# shcmeatic_sst.net
KiCad netlist of a schematic drawn in Altium Designer
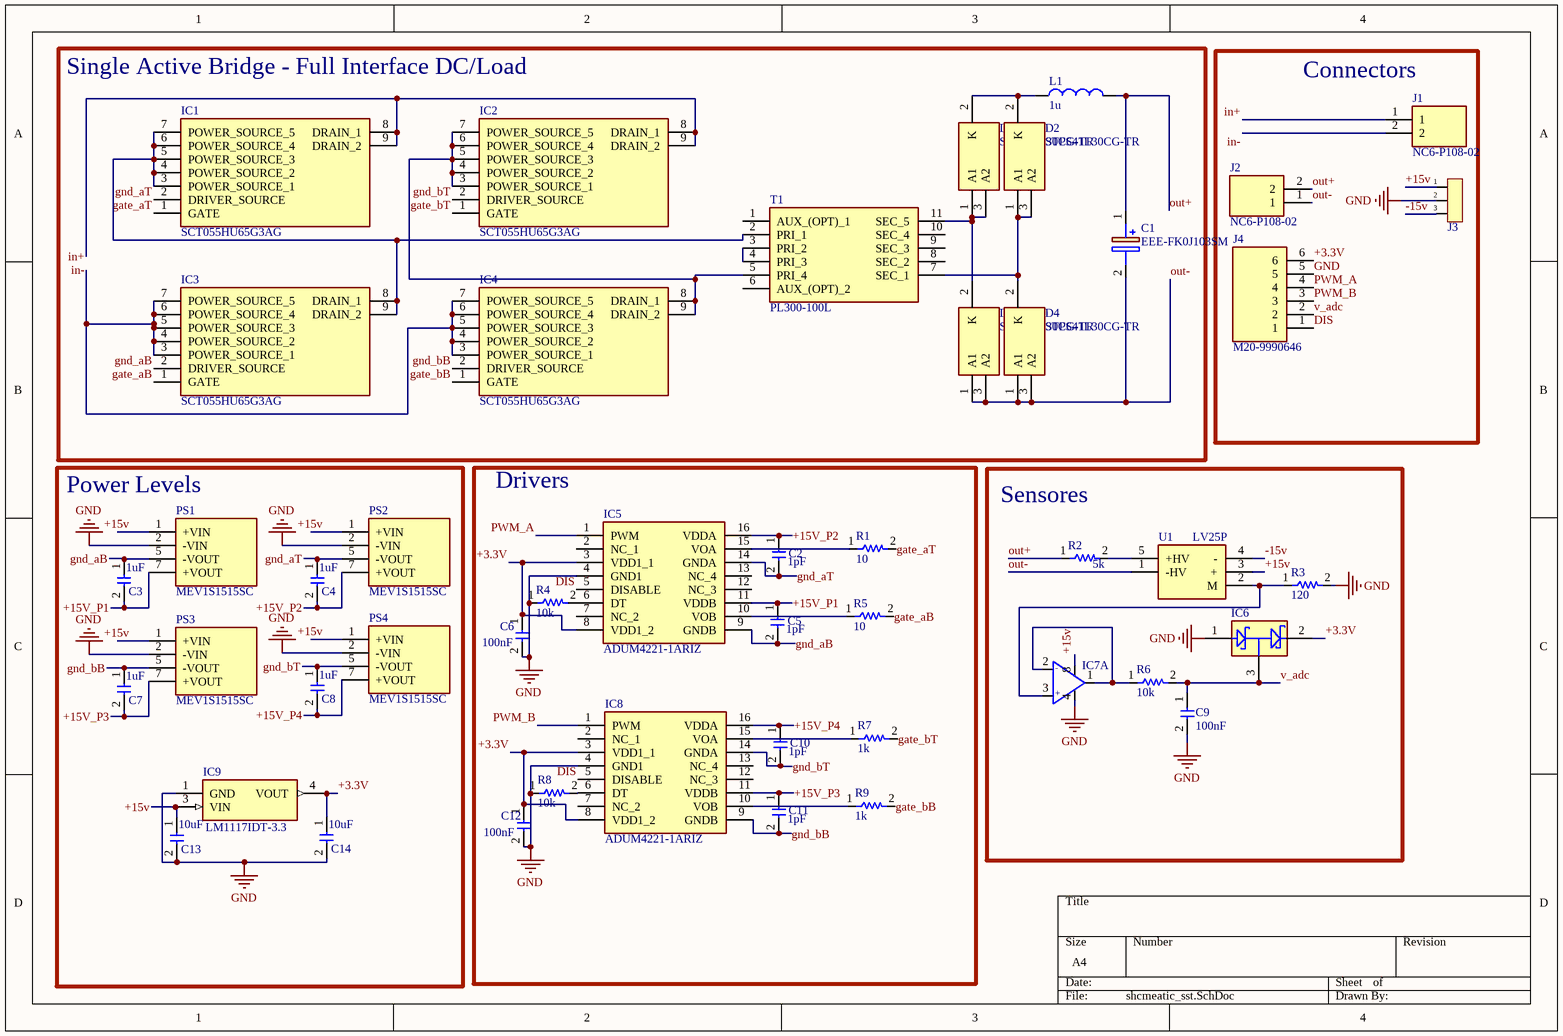
[diagram p0: shcmeatic_sst.SchDoc]

(export (version "E")
  (design (tool "Eeschema 10.0.6"))
  (components
    (comp (ref "C1")
      (value "EEE-FK0J103SM")
      (footprint "r60_mkt_10_100_capacitor_10uF")
      (description "Capacitor Polarised")
      (fields (field (name "MOUSER PART NUMBER") "667-EEE-FK0J103SM"))
      (libsource (lib "*") (part "EEE-FK0J103SM"))
    )
    (comp (ref "C2")
      (value "1pF")
      (footprint "SamacSys:C1206")
      (libsource (lib "Schlib1") (part "Capacitor"))
    )
    (comp (ref "C3")
      (value "1uF")
      (footprint "SamacSys:C1206")
      (libsource (lib "Schlib1") (part "Capacitor"))
    )
    (comp (ref "C4")
      (value "1uF")
      (footprint "SamacSys:C1206")
      (libsource (lib "Schlib1") (part "Capacitor"))
    )
    (comp (ref "C5")
      (value "1pF")
      (footprint "SamacSys:C1206")
      (libsource (lib "Schlib1") (part "Capacitor"))
    )
    (comp (ref "C6")
      (value "100nF")
      (footprint "SamacSys:C1206")
      (libsource (lib "Schlib1") (part "Capacitor"))
    )
    (comp (ref "C7")
      (value "1uF")
      (footprint "SamacSys:C1206")
      (libsource (lib "Schlib1") (part "Capacitor"))
    )
    (comp (ref "C8")
      (value "1uF")
      (footprint "SamacSys:C1206")
      (libsource (lib "Schlib1") (part "Capacitor"))
    )
    (comp (ref "C9")
      (value "100nF")
      (footprint "SamacSys:C1206")
      (libsource (lib "Schlib1") (part "Capacitor"))
    )
    (comp (ref "C10")
      (value "1pF")
      (footprint "SamacSys:C1206")
      (libsource (lib "Schlib1") (part "Capacitor"))
    )
    (comp (ref "C11")
      (value "1pF")
      (footprint "SamacSys:C1206")
      (libsource (lib "Schlib1") (part "Capacitor"))
    )
    (comp (ref "C12")
      (value "100nF")
      (footprint "SamacSys:C1206")
      (libsource (lib "Schlib1") (part "Capacitor"))
    )
    (comp (ref "C13")
      (value "10uF")
      (footprint "T491C")
      (description "tantalum")
      (libsource (lib "Schlib1") (part "Capacitor"))
    )
    (comp (ref "C14")
      (value "10uF")
      (footprint "T491C")
      (description "Tantalum")
      (libsource (lib "Schlib1") (part "Capacitor"))
    )
    (comp (ref "D1")
      (value "STPS41L30CG-TR")
      (footprint "SamacSys:STPS41L30CGTR")
      (description "Schottky Diode")
      (fields (field (name "MOUSER PART NUMBER") "511-STPS41L30CG-TR"))
      (libsource (lib "*") (part "STPS41L30CG-TR"))
    )
    (comp (ref "D2")
      (value "STPS41L30CG-TR")
      (footprint "SamacSys:STPS41L30CGTR")
      (description "Schottky Diode")
      (fields (field (name "MOUSER PART NUMBER") "511-STPS41L30CG-TR"))
      (libsource (lib "*") (part "STPS41L30CG-TR"))
    )
    (comp (ref "D3")
      (value "STPS41L30CG-TR")
      (footprint "SamacSys:STPS41L30CGTR")
      (description "Schottky Diode")
      (fields (field (name "MOUSER PART NUMBER") "511-STPS41L30CG-TR"))
      (libsource (lib "*") (part "STPS41L30CG-TR"))
    )
    (comp (ref "D4")
      (value "STPS41L30CG-TR")
      (footprint "SamacSys:STPS41L30CGTR")
      (description "Schottky Diode")
      (fields (field (name "MOUSER PART NUMBER") "511-STPS41L30CG-TR"))
      (libsource (lib "*") (part "STPS41L30CG-TR"))
    )
    (comp (ref "IC1")
      (value "SCT055HU65G3AG")
      (footprint "SamacSys:SCT055HU65G3AG")
      (description "Integrated Circuit")
      (fields (field (name "MOUSER PART NUMBER") "511-SCT055HU65G3AG"))
      (libsource (lib "*") (part "SCT055HU65G3AG"))
    )
    (comp (ref "IC2")
      (value "SCT055HU65G3AG")
      (footprint "SamacSys:SCT055HU65G3AG")
      (description "Integrated Circuit")
      (fields (field (name "MOUSER PART NUMBER") "511-SCT055HU65G3AG"))
      (libsource (lib "*") (part "SCT055HU65G3AG"))
    )
    (comp (ref "IC3")
      (value "SCT055HU65G3AG")
      (footprint "SamacSys:SCT055HU65G3AG")
      (description "Integrated Circuit")
      (fields (field (name "MOUSER PART NUMBER") "511-SCT055HU65G3AG"))
      (libsource (lib "*") (part "SCT055HU65G3AG"))
    )
    (comp (ref "IC4")
      (value "SCT055HU65G3AG")
      (footprint "SamacSys:SCT055HU65G3AG")
      (description "Integrated Circuit")
      (fields (field (name "MOUSER PART NUMBER") "511-SCT055HU65G3AG"))
      (libsource (lib "*") (part "SCT055HU65G3AG"))
    )
    (comp (ref "IC5")
      (value "ADUM4221-1ARIZ")
      (footprint "SamacSys:SOIC127P1030X264-16N")
      (description "Integrated Circuit")
      (fields (field (name "MOUSER PART NUMBER") "584-ADUM4221-1ARIZ"))
      (libsource (lib "*") (part "ADUM4221-1ARIZ"))
    )
    (comp (ref "IC6") (value "bat54s") (footprint "BAT54S") (libsource (lib "Schlib1") (part "bat54s")))
    (comp (ref "IC7") (value "TSX712IDT") (footprint "SO-8") (libsource (lib "Schlib1") (part "TSX712IDT")))
    (comp (ref "IC8")
      (value "ADUM4221-1ARIZ")
      (footprint "SamacSys:SOIC127P1030X264-16N")
      (description "Integrated Circuit")
      (fields (field (name "MOUSER PART NUMBER") "584-ADUM4221-1ARIZ"))
      (libsource (lib "*") (part "ADUM4221-1ARIZ"))
    )
    (comp (ref "IC9")
      (value "LM1117IDT-3.3")
      (footprint "SamacSys:TO228P991X238-3N")
      (description "Integrated Circuit")
      (fields (field (name "MOUSER PART NUMBER") "926-LM1117IDT-33"))
      (libsource (lib "*") (part "LM1117IDT-3.3"))
    )
    (comp (ref "J1")
      (value "NC6-P108-02")
      (footprint "SamacSys:NC6P10802")
      (description "Connector")
      (fields (field (name "MOUSER PART NUMBER") "571-314376640"))
      (libsource (lib "") (part "NC6-P108-02_1"))
    )
    (comp (ref "J2")
      (value "NC6-P108-02")
      (footprint "SamacSys:NC6P10802")
      (description "Connector")
      (fields (field (name "MOUSER PART NUMBER") "571-314376640"))
      (libsource (lib "*") (part "NC6-P108-02"))
    )
    (comp (ref "J3")
      (value "Conector 1x3P")
      (footprint "Conector 1x3 Screw")
      (libsource (lib "Schlib1") (part "Conector 1x3P"))
    )
    (comp (ref "J4")
      (value "M20-9990646")
      (footprint "SamacSys:HDRV6W64P0X254_1X6_1524X254X864P")
      (description "Connector")
      (fields (field (name "MOUSER PART NUMBER") "855-M20-9990646"))
      (libsource (lib "*") (part "M20-9990646"))
    )
    (comp (ref "L1")
      (value "1u")
      (footprint "bobine_handmade_20mm_diam")
      (description "Inductor")
      (libsource (lib "Simulation Generic Components") (part "Inductor"))
    )
    (comp (ref "PS1")
      (value "MEV1S1515SC")
      (footprint "SamacSys:MEV1S1515SC")
      (description "Power Supply")
      (fields (field (name "MOUSER PART NUMBER") "580-MEV1S1515SC"))
      (libsource (lib "*") (part "MEV1S1515SC"))
    )
    (comp (ref "PS2")
      (value "MEV1S1515SC")
      (footprint "SamacSys:MEV1S1515SC")
      (description "Power Supply")
      (fields (field (name "MOUSER PART NUMBER") "580-MEV1S1515SC"))
      (libsource (lib "*") (part "MEV1S1515SC"))
    )
    (comp (ref "PS3")
      (value "MEV1S1515SC")
      (footprint "SamacSys:MEV1S1515SC")
      (description "Power Supply")
      (fields (field (name "MOUSER PART NUMBER") "580-MEV1S1515SC"))
      (libsource (lib "*") (part "MEV1S1515SC"))
    )
    (comp (ref "PS4")
      (value "MEV1S1515SC")
      (footprint "SamacSys:MEV1S1515SC")
      (description "Power Supply")
      (fields (field (name "MOUSER PART NUMBER") "580-MEV1S1515SC"))
      (libsource (lib "*") (part "MEV1S1515SC"))
    )
    (comp (ref "R1")
      (value "10")
      (footprint "SamacSys:RESC3216X75N")
      (libsource (lib "Schlib1") (part "Resistor"))
    )
    (comp (ref "R2")
      (value "5k")
      (footprint "SamacSys:RESC3216X75N")
      (description "140 mW")
      (libsource (lib "Schlib1") (part "Resistor"))
    )
    (comp (ref "R3")
      (value "120")
      (footprint "SamacSys:RESC3216X75N")
      (description "82.5 mW")
      (libsource (lib "Schlib1") (part "Resistor"))
    )
    (comp (ref "R4")
      (value "10k")
      (footprint "SamacSys:RESC3216X75N")
      (libsource (lib "Schlib1") (part "Resistor"))
    )
    (comp (ref "R5")
      (value "10")
      (footprint "SamacSys:RESC3216X75N")
      (libsource (lib "Schlib1") (part "Resistor"))
    )
    (comp (ref "R6")
      (value "10k")
      (footprint "SamacSys:RESC3216X75N")
      (libsource (lib "Schlib1") (part "Resistor"))
    )
    (comp (ref "R7")
      (value "1k")
      (footprint "SamacSys:RESC3216X75N")
      (libsource (lib "Schlib1") (part "Resistor"))
    )
    (comp (ref "R8")
      (value "10k")
      (footprint "SamacSys:RESC3216X75N")
      (libsource (lib "Schlib1") (part "Resistor"))
    )
    (comp (ref "R9")
      (value "1k")
      (footprint "SamacSys:RESC3216X75N")
      (libsource (lib "Schlib1") (part "Resistor"))
    )
    (comp (ref "T1")
      (value "PL300-100L")
      (footprint "SamacSys:PL300100L")
      (description "Transformer")
      (fields (field (name "MOUSER PART NUMBER") "994-PL300-100L"))
      (libsource (lib "*") (part "PL300-100L"))
    )
    (comp (ref "U1")
      (value "LV25P")
      (footprint "LV-25-P/LV-20-P")
      (description "Undefined or Miscellaneous")
      (libsource (lib "Schlib1") (part "LV25P"))
    )
  )
  (nets
    (net (code "1") (name "/+3.3V") (class "Default")
      (node (ref "C12") (pin "1") (pinfunction "1_1") (pintype "passive"))
      (node (ref "C14") (pin "1") (pinfunction "1_1") (pintype "passive"))
      (node (ref "C6") (pin "1") (pinfunction "1_1") (pintype "passive"))
      (node (ref "IC5") (pin "3") (pinfunction "VDD1_1_3") (pintype "passive"))
      (node (ref "IC5") (pin "8") (pinfunction "VDD1_2_8") (pintype "passive"))
      (node (ref "IC6") (pin "2") (pinfunction "OUT_2") (pintype "passive"))
      (node (ref "IC8") (pin "3") (pinfunction "VDD1_1_3") (pintype "passive"))
      (node (ref "IC8") (pin "8") (pinfunction "VDD1_2_8") (pintype "passive"))
      (node (ref "IC9") (pin "4") (pinfunction "VOUT_4") (pintype "output"))
      (node (ref "J4") (pin "6") (pinfunction "6_6") (pintype "passive"))
    )
    (net (code "2") (name "/+15V_P1") (class "Default")
      (node (ref "C3") (pin "2") (pinfunction "2_2") (pintype "passive"))
      (node (ref "C5") (pin "1") (pinfunction "1_1") (pintype "passive"))
      (node (ref "IC5") (pin "11") (pinfunction "VDDB_11") (pintype "passive"))
      (node (ref "PS1") (pin "7") (pinfunction "+VOUT_7") (pintype "passive"))
    )
    (net (code "3") (name "/+15V_P2") (class "Default")
      (node (ref "C2") (pin "1") (pinfunction "1_1") (pintype "passive"))
      (node (ref "C4") (pin "2") (pinfunction "2_2") (pintype "passive"))
      (node (ref "IC5") (pin "16") (pinfunction "VDDA_16") (pintype "passive"))
      (node (ref "PS2") (pin "7") (pinfunction "+VOUT_7") (pintype "passive"))
    )
    (net (code "4") (name "/+15V_P3") (class "Default")
      (node (ref "C11") (pin "1") (pinfunction "1_1") (pintype "passive"))
      (node (ref "C7") (pin "2") (pinfunction "2_2") (pintype "passive"))
      (node (ref "IC8") (pin "11") (pinfunction "VDDB_11") (pintype "passive"))
      (node (ref "PS3") (pin "7") (pinfunction "+VOUT_7") (pintype "passive"))
    )
    (net (code "5") (name "/+15V_P4") (class "Default")
      (node (ref "C10") (pin "1") (pinfunction "1_1") (pintype "passive"))
      (node (ref "C8") (pin "2") (pinfunction "2_2") (pintype "passive"))
      (node (ref "IC8") (pin "16") (pinfunction "VDDA_16") (pintype "passive"))
      (node (ref "PS4") (pin "7") (pinfunction "+VOUT_7") (pintype "passive"))
    )
    (net (code "6") (name "/+15v") (class "Default")
      (node (ref "C13") (pin "1") (pinfunction "1_1") (pintype "passive"))
      (node (ref "IC7") (pin "8") (pinfunction "8_8") (pintype "passive"))
      (node (ref "IC9") (pin "3") (pinfunction "VIN_3") (pintype "input"))
      (node (ref "J3") (pin "1") (pinfunction "1_1") (pintype "passive"))
      (node (ref "PS1") (pin "1") (pinfunction "+VIN_1") (pintype "passive"))
      (node (ref "PS2") (pin "1") (pinfunction "+VIN_1") (pintype "passive"))
      (node (ref "PS3") (pin "1") (pinfunction "+VIN_1") (pintype "passive"))
      (node (ref "PS4") (pin "1") (pinfunction "+VIN_1") (pintype "passive"))
      (node (ref "U1") (pin "3") (pinfunction "+_3") (pintype "passive"))
    )
    (net (code "7") (name "/-15v") (class "Default")
      (node (ref "J3") (pin "3") (pinfunction "3_3") (pintype "passive"))
      (node (ref "U1") (pin "4") (pinfunction "-_4") (pintype "passive"))
    )
    (net (code "9") (name "/DIS") (class "Default")
      (node (ref "IC5") (pin "5") (pinfunction "DISABLE_5") (pintype "passive"))
      (node (ref "IC8") (pin "5") (pinfunction "DISABLE_5") (pintype "passive"))
      (node (ref "J4") (pin "1") (pinfunction "1_1") (pintype "passive"))
    )
    (net (code "10") (name "/PWM_A") (class "Default")
      (node (ref "IC5") (pin "1") (pinfunction "PWM_1") (pintype "passive"))
      (node (ref "J4") (pin "4") (pinfunction "4_4") (pintype "passive"))
    )
    (net (code "11") (name "/PWM_B") (class "Default")
      (node (ref "IC8") (pin "1") (pinfunction "PWM_1") (pintype "passive"))
      (node (ref "J4") (pin "3") (pinfunction "3_3") (pintype "passive"))
    )
    (net (code "12") (name "/gate_aB") (class "Default")
      (node (ref "IC3") (pin "1") (pinfunction "GATE_1") (pintype "passive"))
      (node (ref "R5") (pin "2") (pinfunction "2_2") (pintype "passive"))
    )
    (net (code "13") (name "/gate_aT") (class "Default")
      (node (ref "IC1") (pin "1") (pinfunction "GATE_1") (pintype "passive"))
      (node (ref "R1") (pin "2") (pinfunction "2_2") (pintype "passive"))
    )
    (net (code "14") (name "/gate_bB") (class "Default")
      (node (ref "IC4") (pin "1") (pinfunction "GATE_1") (pintype "passive"))
      (node (ref "R9") (pin "2") (pinfunction "2_2") (pintype "passive"))
    )
    (net (code "15") (name "/gate_bT") (class "Default")
      (node (ref "IC2") (pin "1") (pinfunction "GATE_1") (pintype "passive"))
      (node (ref "R7") (pin "2") (pinfunction "2_2") (pintype "passive"))
    )
    (net (code "16") (name "/gnd_aB") (class "Default")
      (node (ref "C3") (pin "1") (pinfunction "1_1") (pintype "passive"))
      (node (ref "C5") (pin "2") (pinfunction "2_2") (pintype "passive"))
      (node (ref "IC3") (pin "2") (pinfunction "DRIVER_SOURCE_2") (pintype "passive"))
      (node (ref "IC5") (pin "9") (pinfunction "GNDB_9") (pintype "passive"))
      (node (ref "PS1") (pin "5") (pinfunction "-VOUT_5") (pintype "passive"))
    )
    (net (code "17") (name "/gnd_aT") (class "Default")
      (node (ref "C2") (pin "2") (pinfunction "2_2") (pintype "passive"))
      (node (ref "C4") (pin "1") (pinfunction "1_1") (pintype "passive"))
      (node (ref "IC1") (pin "2") (pinfunction "DRIVER_SOURCE_2") (pintype "passive"))
      (node (ref "IC5") (pin "14") (pinfunction "GNDA_14") (pintype "passive"))
      (node (ref "PS2") (pin "5") (pinfunction "-VOUT_5") (pintype "passive"))
    )
    (net (code "18") (name "/gnd_bB") (class "Default")
      (node (ref "C11") (pin "2") (pinfunction "2_2") (pintype "passive"))
      (node (ref "C7") (pin "1") (pinfunction "1_1") (pintype "passive"))
      (node (ref "IC4") (pin "2") (pinfunction "DRIVER_SOURCE_2") (pintype "passive"))
      (node (ref "IC8") (pin "9") (pinfunction "GNDB_9") (pintype "passive"))
      (node (ref "PS3") (pin "5") (pinfunction "-VOUT_5") (pintype "passive"))
    )
    (net (code "19") (name "/gnd_bT") (class "Default")
      (node (ref "C10") (pin "2") (pinfunction "2_2") (pintype "passive"))
      (node (ref "C8") (pin "1") (pinfunction "1_1") (pintype "passive"))
      (node (ref "IC2") (pin "2") (pinfunction "DRIVER_SOURCE_2") (pintype "passive"))
      (node (ref "IC8") (pin "14") (pinfunction "GNDA_14") (pintype "passive"))
      (node (ref "PS4") (pin "5") (pinfunction "-VOUT_5") (pintype "passive"))
    )
    (net (code "20") (name "/in+") (class "Default")
      (node (ref "IC1") (pin "8") (pinfunction "DRAIN_1_8") (pintype "passive"))
      (node (ref "IC1") (pin "9") (pinfunction "DRAIN_2_9") (pintype "passive"))
      (node (ref "IC2") (pin "8") (pinfunction "DRAIN_1_8") (pintype "passive"))
      (node (ref "IC2") (pin "9") (pinfunction "DRAIN_2_9") (pintype "passive"))
      (node (ref "J1") (pin "1") (pinfunction "1_1") (pintype "passive"))
    )
    (net (code "21") (name "/in-") (class "Default")
      (node (ref "IC3") (pin "3") (pinfunction "POWER_SOURCE_1_3") (pintype "passive"))
      (node (ref "IC3") (pin "4") (pinfunction "POWER_SOURCE_2_4") (pintype "passive"))
      (node (ref "IC3") (pin "5") (pinfunction "POWER_SOURCE_3_5") (pintype "passive"))
      (node (ref "IC3") (pin "6") (pinfunction "POWER_SOURCE_4_6") (pintype "passive"))
      (node (ref "IC3") (pin "7") (pinfunction "POWER_SOURCE_5_7") (pintype "passive"))
      (node (ref "IC4") (pin "3") (pinfunction "POWER_SOURCE_1_3") (pintype "passive"))
      (node (ref "IC4") (pin "4") (pinfunction "POWER_SOURCE_2_4") (pintype "passive"))
      (node (ref "IC4") (pin "5") (pinfunction "POWER_SOURCE_3_5") (pintype "passive"))
      (node (ref "IC4") (pin "6") (pinfunction "POWER_SOURCE_4_6") (pintype "passive"))
      (node (ref "IC4") (pin "7") (pinfunction "POWER_SOURCE_5_7") (pintype "passive"))
      (node (ref "J1") (pin "2") (pinfunction "2_2") (pintype "passive"))
    )
    (net (code "22") (name "/out+") (class "Default")
      (node (ref "C1") (pin "1") (pinfunction "+_1") (pintype "passive"))
      (node (ref "J2") (pin "2") (pinfunction "2_2") (pintype "passive"))
      (node (ref "L1") (pin "2") (pinfunction "2_2") (pintype "passive"))
      (node (ref "R2") (pin "1") (pinfunction "6_1") (pintype "passive"))
    )
    (net (code "23") (name "/out-") (class "Default")
      (node (ref "C1") (pin "2") (pinfunction "-_2") (pintype "passive"))
      (node (ref "D3") (pin "1") (pinfunction "A1_1") (pintype "passive"))
      (node (ref "D3") (pin "3") (pinfunction "A2_3") (pintype "passive"))
      (node (ref "D4") (pin "1") (pinfunction "A1_1") (pintype "passive"))
      (node (ref "D4") (pin "3") (pinfunction "A2_3") (pintype "passive"))
      (node (ref "J2") (pin "1") (pinfunction "1_1") (pintype "passive"))
      (node (ref "U1") (pin "1") (pinfunction "-HV_1") (pintype "passive"))
    )
    (net (code "24") (name "/v_adc") (class "Default")
      (node (ref "C9") (pin "1") (pinfunction "1_1") (pintype "passive"))
      (node (ref "IC6") (pin "3") (pinfunction "COM_3") (pintype "passive"))
      (node (ref "J4") (pin "2") (pinfunction "2_2") (pintype "passive"))
      (node (ref "R6") (pin "2") (pinfunction "2_2") (pintype "passive"))
    )
    (net (code "25") (name "GND") (class "Default")
      (node (ref "C12") (pin "2") (pinfunction "2_2") (pintype "passive"))
      (node (ref "C13") (pin "2") (pinfunction "2_2") (pintype "passive"))
      (node (ref "C14") (pin "2") (pinfunction "2_2") (pintype "passive"))
      (node (ref "C6") (pin "2") (pinfunction "2_2") (pintype "passive"))
      (node (ref "C9") (pin "2") (pinfunction "2_2") (pintype "passive"))
      (node (ref "IC5") (pin "4") (pinfunction "GND1_4") (pintype "passive"))
      (node (ref "IC6") (pin "1") (pinfunction "IN_1") (pintype "passive"))
      (node (ref "IC7") (pin "4") (pinfunction "4_4") (pintype "passive"))
      (node (ref "IC8") (pin "4") (pinfunction "GND1_4") (pintype "passive"))
      (node (ref "IC9") (pin "1") (pinfunction "GND_1") (pintype "power_in"))
      (node (ref "J3") (pin "2") (pinfunction "2_2") (pintype "passive"))
      (node (ref "J4") (pin "5") (pinfunction "5_5") (pintype "passive"))
      (node (ref "PS1") (pin "2") (pinfunction "-VIN_2") (pintype "passive"))
      (node (ref "PS2") (pin "2") (pinfunction "-VIN_2") (pintype "passive"))
      (node (ref "PS3") (pin "2") (pinfunction "-VIN_2") (pintype "passive"))
      (node (ref "PS4") (pin "2") (pinfunction "-VIN_2") (pintype "passive"))
      (node (ref "R3") (pin "2") (pinfunction "2_2") (pintype "passive"))
      (node (ref "R4") (pin "1") (pinfunction "6_1") (pintype "passive"))
      (node (ref "R8") (pin "1") (pinfunction "6_1") (pintype "passive"))
    )
    (net (code "26") (name "Net-(D1-A1)") (class "Default")
      (node (ref "D1") (pin "1") (pinfunction "A1_1") (pintype "passive"))
      (node (ref "D1") (pin "3") (pinfunction "A2_3") (pintype "passive"))
      (node (ref "D3") (pin "2") (pinfunction "K_2") (pintype "passive"))
      (node (ref "T1") (pin "11") (pinfunction "SEC_5_11") (pintype "passive"))
    )
    (net (code "27") (name "Net-(D1-K)") (class "Default")
      (node (ref "D1") (pin "2") (pinfunction "K_2") (pintype "passive"))
      (node (ref "D2") (pin "2") (pinfunction "K_2") (pintype "passive"))
      (node (ref "L1") (pin "1") (pinfunction "1_1") (pintype "passive"))
    )
    (net (code "28") (name "Net-(D2-A1)") (class "Default")
      (node (ref "D2") (pin "1") (pinfunction "A1_1") (pintype "passive"))
      (node (ref "D2") (pin "3") (pinfunction "A2_3") (pintype "passive"))
      (node (ref "D4") (pin "2") (pinfunction "K_2") (pintype "passive"))
      (node (ref "T1") (pin "7") (pinfunction "SEC_1_7") (pintype "passive"))
    )
    (net (code "29") (name "Net-(IC1-POWER_SOURCE_1)") (class "Default")
      (node (ref "IC1") (pin "3") (pinfunction "POWER_SOURCE_1_3") (pintype "passive"))
      (node (ref "IC1") (pin "4") (pinfunction "POWER_SOURCE_2_4") (pintype "passive"))
      (node (ref "IC1") (pin "5") (pinfunction "POWER_SOURCE_3_5") (pintype "passive"))
      (node (ref "IC1") (pin "6") (pinfunction "POWER_SOURCE_4_6") (pintype "passive"))
      (node (ref "IC1") (pin "7") (pinfunction "POWER_SOURCE_5_7") (pintype "passive"))
      (node (ref "IC3") (pin "8") (pinfunction "DRAIN_1_8") (pintype "passive"))
      (node (ref "IC3") (pin "9") (pinfunction "DRAIN_2_9") (pintype "passive"))
      (node (ref "T1") (pin "2") (pinfunction "PRI_1_2") (pintype "passive"))
    )
    (net (code "30") (name "Net-(IC2-POWER_SOURCE_1)") (class "Default")
      (node (ref "IC2") (pin "3") (pinfunction "POWER_SOURCE_1_3") (pintype "passive"))
      (node (ref "IC2") (pin "4") (pinfunction "POWER_SOURCE_2_4") (pintype "passive"))
      (node (ref "IC2") (pin "5") (pinfunction "POWER_SOURCE_3_5") (pintype "passive"))
      (node (ref "IC2") (pin "6") (pinfunction "POWER_SOURCE_4_6") (pintype "passive"))
      (node (ref "IC2") (pin "7") (pinfunction "POWER_SOURCE_5_7") (pintype "passive"))
      (node (ref "IC4") (pin "8") (pinfunction "DRAIN_1_8") (pintype "passive"))
      (node (ref "IC4") (pin "9") (pinfunction "DRAIN_2_9") (pintype "passive"))
      (node (ref "T1") (pin "5") (pinfunction "PRI_4_5") (pintype "passive"))
    )
    (net (code "31") (name "Net-(IC5-DT)") (class "Default")
      (node (ref "IC5") (pin "6") (pinfunction "DT_6") (pintype "passive"))
      (node (ref "R4") (pin "2") (pinfunction "2_2") (pintype "passive"))
    )
    (net (code "32") (name "Net-(IC5-VOA)") (class "Default")
      (node (ref "IC5") (pin "15") (pinfunction "VOA_15") (pintype "passive"))
      (node (ref "R1") (pin "1") (pinfunction "6_1") (pintype "passive"))
    )
    (net (code "33") (name "Net-(IC5-VOB)") (class "Default")
      (node (ref "IC5") (pin "10") (pinfunction "VOB_10") (pintype "passive"))
      (node (ref "R5") (pin "1") (pinfunction "6_1") (pintype "passive"))
    )
    (net (code "34") (name "Net-(IC8-DT)") (class "Default")
      (node (ref "IC8") (pin "6") (pinfunction "DT_6") (pintype "passive"))
      (node (ref "R8") (pin "2") (pinfunction "2_2") (pintype "passive"))
    )
    (net (code "35") (name "Net-(IC8-VOA)") (class "Default")
      (node (ref "IC8") (pin "15") (pinfunction "VOA_15") (pintype "passive"))
      (node (ref "R7") (pin "1") (pinfunction "6_1") (pintype "passive"))
    )
    (net (code "36") (name "Net-(IC8-VOB)") (class "Default")
      (node (ref "IC8") (pin "10") (pinfunction "VOB_10") (pintype "passive"))
      (node (ref "R9") (pin "1") (pinfunction "6_1") (pintype "passive"))
    )
    (net (code "37") (name "Net-(R3-6)") (class "Default")
      (node (ref "IC7") (pin "3") (pinfunction "3_3") (pintype "passive"))
      (node (ref "R3") (pin "1") (pinfunction "6_1") (pintype "passive"))
      (node (ref "U1") (pin "2") (pinfunction "M_2") (pintype "passive"))
    )
    (net (code "38") (name "Net-(R6-6)") (class "Default")
      (node (ref "IC7") (pin "1") (pinfunction "1_1") (pintype "passive"))
      (node (ref "IC7") (pin "2") (pinfunction "2_2") (pintype "passive"))
      (node (ref "R6") (pin "1") (pinfunction "6_1") (pintype "passive"))
    )
    (net (code "39") (name "Net-(T1-PRI_2)") (class "Default")
      (node (ref "T1") (pin "3") (pinfunction "PRI_2_3") (pintype "passive"))
      (node (ref "T1") (pin "4") (pinfunction "PRI_3_4") (pintype "passive"))
    )
    (net (code "40") (name "Net-(U1-+HV)") (class "Default")
      (node (ref "R2") (pin "2") (pinfunction "2_2") (pintype "passive"))
      (node (ref "U1") (pin "5") (pinfunction "+HV_5") (pintype "passive"))
    )
    (net (code "41") (name "unconnected-(IC5-NC_1-Pad2)") (class "Default")
      (node (ref "IC5") (pin "2") (pinfunction "NC_1_2") (pintype "passive"))
    )
    (net (code "42") (name "unconnected-(IC5-NC_2-Pad7)") (class "Default")
      (node (ref "IC5") (pin "7") (pinfunction "NC_2_7") (pintype "passive"))
    )
    (net (code "43") (name "unconnected-(IC5-NC_3-Pad12)") (class "Default")
      (node (ref "IC5") (pin "12") (pinfunction "NC_3_12") (pintype "passive"))
    )
    (net (code "44") (name "unconnected-(IC5-NC_4-Pad13)") (class "Default")
      (node (ref "IC5") (pin "13") (pinfunction "NC_4_13") (pintype "passive"))
    )
    (net (code "45") (name "unconnected-(IC8-NC_1-Pad2)") (class "Default")
      (node (ref "IC8") (pin "2") (pinfunction "NC_1_2") (pintype "passive"))
    )
    (net (code "46") (name "unconnected-(IC8-NC_2-Pad7)") (class "Default")
      (node (ref "IC8") (pin "7") (pinfunction "NC_2_7") (pintype "passive"))
    )
    (net (code "47") (name "unconnected-(IC8-NC_3-Pad12)") (class "Default")
      (node (ref "IC8") (pin "12") (pinfunction "NC_3_12") (pintype "passive"))
    )
    (net (code "48") (name "unconnected-(IC8-NC_4-Pad13)") (class "Default")
      (node (ref "IC8") (pin "13") (pinfunction "NC_4_13") (pintype "passive"))
    )
    (net (code "49") (name "unconnected-(T1-AUX_(OPT)_1-Pad1)") (class "Default")
      (node (ref "T1") (pin "1") (pinfunction "AUX_(OPT)_1_1") (pintype "passive"))
    )
    (net (code "50") (name "unconnected-(T1-AUX_(OPT)_2-Pad6)") (class "Default")
      (node (ref "T1") (pin "6") (pinfunction "AUX_(OPT)_2_6") (pintype "passive"))
    )
    (net (code "51") (name "unconnected-(T1-SEC_2-Pad8)") (class "Default")
      (node (ref "T1") (pin "8") (pinfunction "SEC_2_8") (pintype "passive"))
    )
    (net (code "52") (name "unconnected-(T1-SEC_3-Pad9)") (class "Default")
      (node (ref "T1") (pin "9") (pinfunction "SEC_3_9") (pintype "passive"))
    )
    (net (code "53") (name "unconnected-(T1-SEC_4-Pad10)") (class "Default")
      (node (ref "T1") (pin "10") (pinfunction "SEC_4_10") (pintype "passive"))
    )
  )
)
